# Flexbus_Cable_-_Flipped.net
KiCad netlist of a schematic drawn in EasyEDA Pro
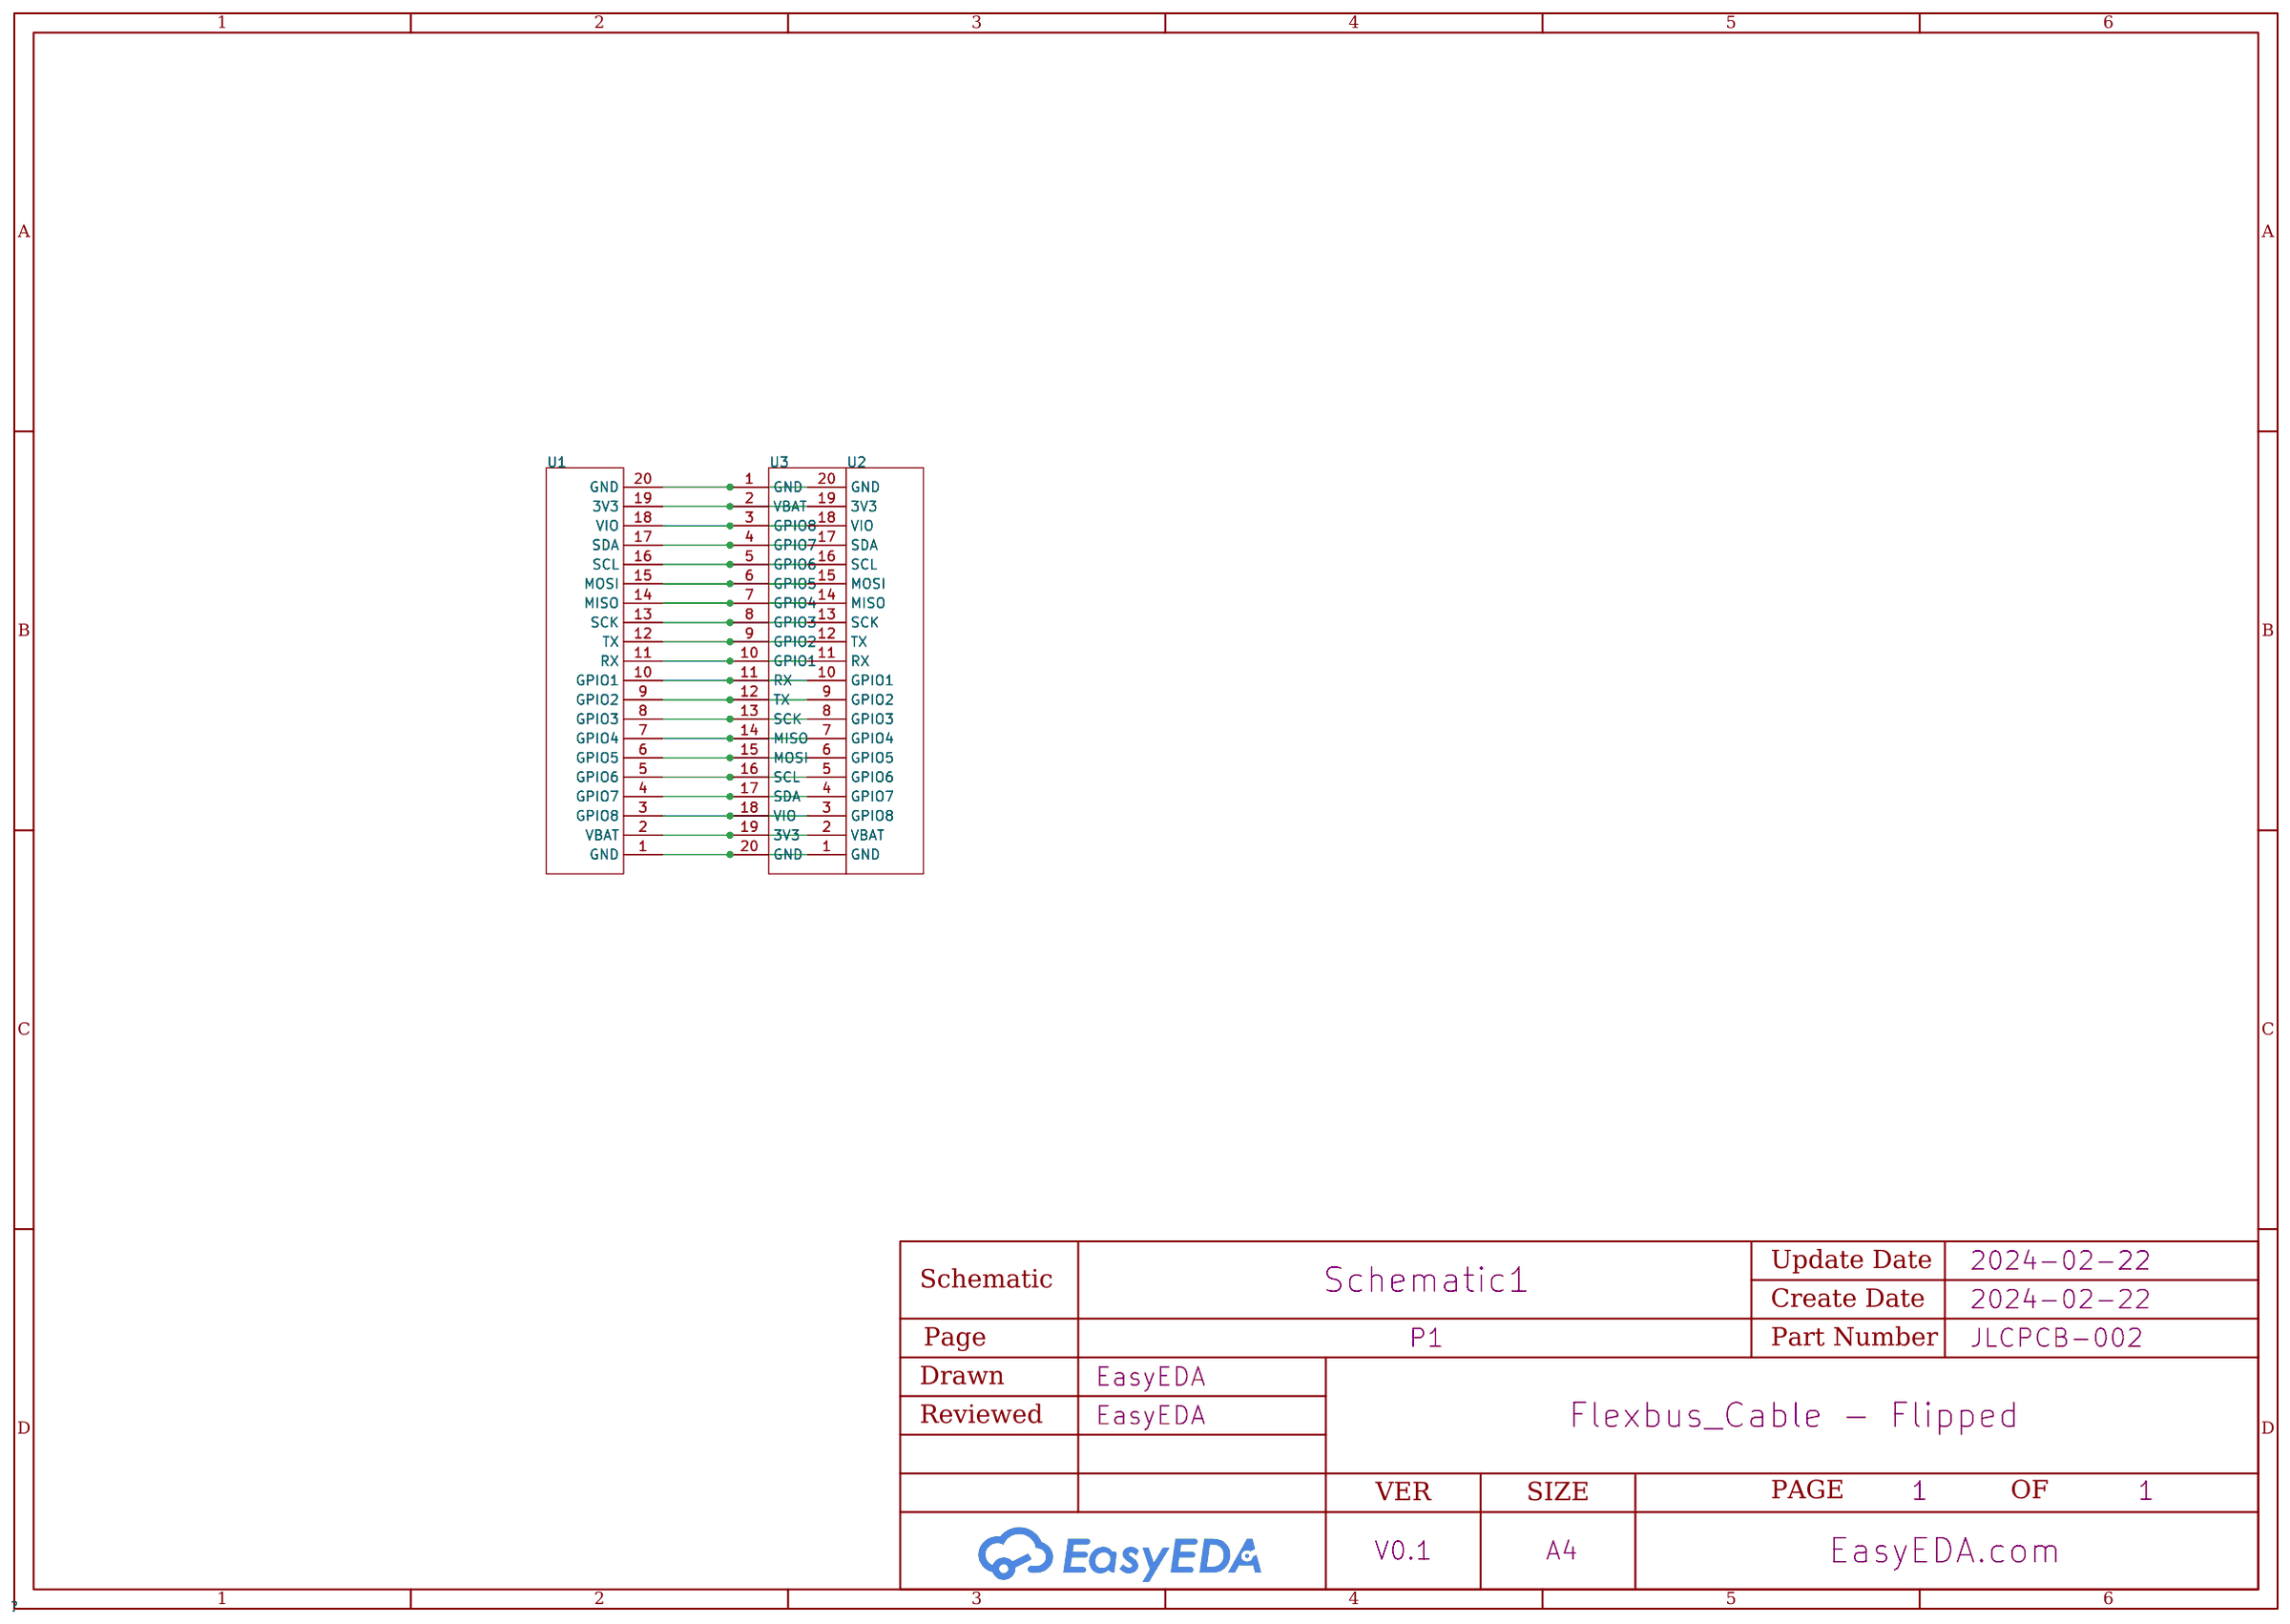
[diagram p0: schematic sheet]

(export (version "E")
  (design (tool "Eeschema 10.0.6"))
  (components
    (comp (ref "U1")
      (value "~")
      (footprint "easyedapro:FPC 0.5mm 20P")
      (libsource (lib "easyedapro") (part "FlexBus FPC 0.5mm 20P"))
    )
    (comp (ref "U2")
      (value "~")
      (footprint "easyedapro:FPC 0.5mm 20P")
      (libsource (lib "easyedapro") (part "FlexBus FPC 0.5mm 20P"))
    )
    (comp (ref "U3")
      (value "~")
      (footprint "easyedapro:FPC 0.5mm 20P")
      (libsource (lib "easyedapro") (part "FlexBus FPC 0.5mm 20P"))
    )
  )
  (nets
    (net (code "1") (name "Net-(U1-3V3)") (class "Default")
      (node (ref "U1") (pin "19") (pinfunction "3V3_19") (pintype "input"))
      (node (ref "U2") (pin "19") (pinfunction "3V3_19") (pintype "input"))
      (node (ref "U3") (pin "2") (pinfunction "VBAT_2") (pintype "input"))
    )
    (net (code "2") (name "Net-(U1-GND-Pad1)") (class "Default")
      (node (ref "U1") (pin "1") (pinfunction "GND_1") (pintype "input"))
      (node (ref "U2") (pin "1") (pinfunction "GND_1") (pintype "input"))
      (node (ref "U3") (pin "20") (pinfunction "GND_20") (pintype "input"))
    )
    (net (code "3") (name "Net-(U1-GND-Pad20)") (class "Default")
      (node (ref "U1") (pin "20") (pinfunction "GND_20") (pintype "input"))
      (node (ref "U2") (pin "20") (pinfunction "GND_20") (pintype "input"))
      (node (ref "U3") (pin "1") (pinfunction "GND_1") (pintype "input"))
    )
    (net (code "4") (name "Net-(U1-GPIO1)") (class "Default")
      (node (ref "U1") (pin "10") (pinfunction "GPIO1_10") (pintype "input"))
      (node (ref "U2") (pin "10") (pinfunction "GPIO1_10") (pintype "input"))
      (node (ref "U3") (pin "11") (pinfunction "RX_11") (pintype "input"))
    )
    (net (code "5") (name "Net-(U1-GPIO2)") (class "Default")
      (node (ref "U1") (pin "9") (pinfunction "GPIO2_9") (pintype "input"))
      (node (ref "U2") (pin "9") (pinfunction "GPIO2_9") (pintype "input"))
      (node (ref "U3") (pin "12") (pinfunction "TX_12") (pintype "input"))
    )
    (net (code "6") (name "Net-(U1-GPIO3)") (class "Default")
      (node (ref "U1") (pin "8") (pinfunction "GPIO3_8") (pintype "input"))
      (node (ref "U2") (pin "8") (pinfunction "GPIO3_8") (pintype "input"))
      (node (ref "U3") (pin "13") (pinfunction "SCK_13") (pintype "input"))
    )
    (net (code "7") (name "Net-(U1-GPIO4)") (class "Default")
      (node (ref "U1") (pin "7") (pinfunction "GPIO4_7") (pintype "input"))
      (node (ref "U2") (pin "7") (pinfunction "GPIO4_7") (pintype "input"))
      (node (ref "U3") (pin "14") (pinfunction "MISO_14") (pintype "input"))
    )
    (net (code "8") (name "Net-(U1-GPIO5)") (class "Default")
      (node (ref "U1") (pin "6") (pinfunction "GPIO5_6") (pintype "input"))
      (node (ref "U2") (pin "6") (pinfunction "GPIO5_6") (pintype "input"))
      (node (ref "U3") (pin "15") (pinfunction "MOSI_15") (pintype "input"))
    )
    (net (code "9") (name "Net-(U1-GPIO6)") (class "Default")
      (node (ref "U1") (pin "5") (pinfunction "GPIO6_5") (pintype "input"))
      (node (ref "U2") (pin "5") (pinfunction "GPIO6_5") (pintype "input"))
      (node (ref "U3") (pin "16") (pinfunction "SCL_16") (pintype "input"))
    )
    (net (code "10") (name "Net-(U1-GPIO7)") (class "Default")
      (node (ref "U1") (pin "4") (pinfunction "GPIO7_4") (pintype "input"))
      (node (ref "U2") (pin "4") (pinfunction "GPIO7_4") (pintype "input"))
      (node (ref "U3") (pin "17") (pinfunction "SDA_17") (pintype "input"))
    )
    (net (code "11") (name "Net-(U1-GPIO8)") (class "Default")
      (node (ref "U1") (pin "3") (pinfunction "GPIO8_3") (pintype "input"))
      (node (ref "U2") (pin "3") (pinfunction "GPIO8_3") (pintype "input"))
      (node (ref "U3") (pin "18") (pinfunction "VIO_18") (pintype "input"))
    )
    (net (code "12") (name "Net-(U1-MISO)") (class "Default")
      (node (ref "U1") (pin "14") (pinfunction "MISO_14") (pintype "input"))
      (node (ref "U2") (pin "14") (pinfunction "MISO_14") (pintype "input"))
      (node (ref "U3") (pin "7") (pinfunction "GPIO4_7") (pintype "input"))
    )
    (net (code "13") (name "Net-(U1-MOSI)") (class "Default")
      (node (ref "U1") (pin "15") (pinfunction "MOSI_15") (pintype "input"))
      (node (ref "U2") (pin "15") (pinfunction "MOSI_15") (pintype "input"))
      (node (ref "U3") (pin "6") (pinfunction "GPIO5_6") (pintype "input"))
    )
    (net (code "14") (name "Net-(U1-RX)") (class "Default")
      (node (ref "U1") (pin "11") (pinfunction "RX_11") (pintype "input"))
      (node (ref "U2") (pin "11") (pinfunction "RX_11") (pintype "input"))
      (node (ref "U3") (pin "10") (pinfunction "GPIO1_10") (pintype "input"))
    )
    (net (code "15") (name "Net-(U1-SCK)") (class "Default")
      (node (ref "U1") (pin "13") (pinfunction "SCK_13") (pintype "input"))
      (node (ref "U2") (pin "13") (pinfunction "SCK_13") (pintype "input"))
      (node (ref "U3") (pin "8") (pinfunction "GPIO3_8") (pintype "input"))
    )
    (net (code "16") (name "Net-(U1-SCL)") (class "Default")
      (node (ref "U1") (pin "16") (pinfunction "SCL_16") (pintype "input"))
      (node (ref "U2") (pin "16") (pinfunction "SCL_16") (pintype "input"))
      (node (ref "U3") (pin "5") (pinfunction "GPIO6_5") (pintype "input"))
    )
    (net (code "17") (name "Net-(U1-SDA)") (class "Default")
      (node (ref "U1") (pin "17") (pinfunction "SDA_17") (pintype "input"))
      (node (ref "U2") (pin "17") (pinfunction "SDA_17") (pintype "input"))
      (node (ref "U3") (pin "4") (pinfunction "GPIO7_4") (pintype "input"))
    )
    (net (code "18") (name "Net-(U1-TX)") (class "Default")
      (node (ref "U1") (pin "12") (pinfunction "TX_12") (pintype "input"))
      (node (ref "U2") (pin "12") (pinfunction "TX_12") (pintype "input"))
      (node (ref "U3") (pin "9") (pinfunction "GPIO2_9") (pintype "input"))
    )
    (net (code "19") (name "Net-(U1-VBAT)") (class "Default")
      (node (ref "U1") (pin "2") (pinfunction "VBAT_2") (pintype "input"))
      (node (ref "U2") (pin "2") (pinfunction "VBAT_2") (pintype "input"))
      (node (ref "U3") (pin "19") (pinfunction "3V3_19") (pintype "input"))
    )
    (net (code "20") (name "Net-(U1-VIO)") (class "Default")
      (node (ref "U1") (pin "18") (pinfunction "VIO_18") (pintype "input"))
      (node (ref "U2") (pin "18") (pinfunction "VIO_18") (pintype "input"))
      (node (ref "U3") (pin "3") (pinfunction "GPIO8_3") (pintype "input"))
    )
  )
)
